# Terrarium.net
KiCad netlist of a schematic drawn in EAGLE
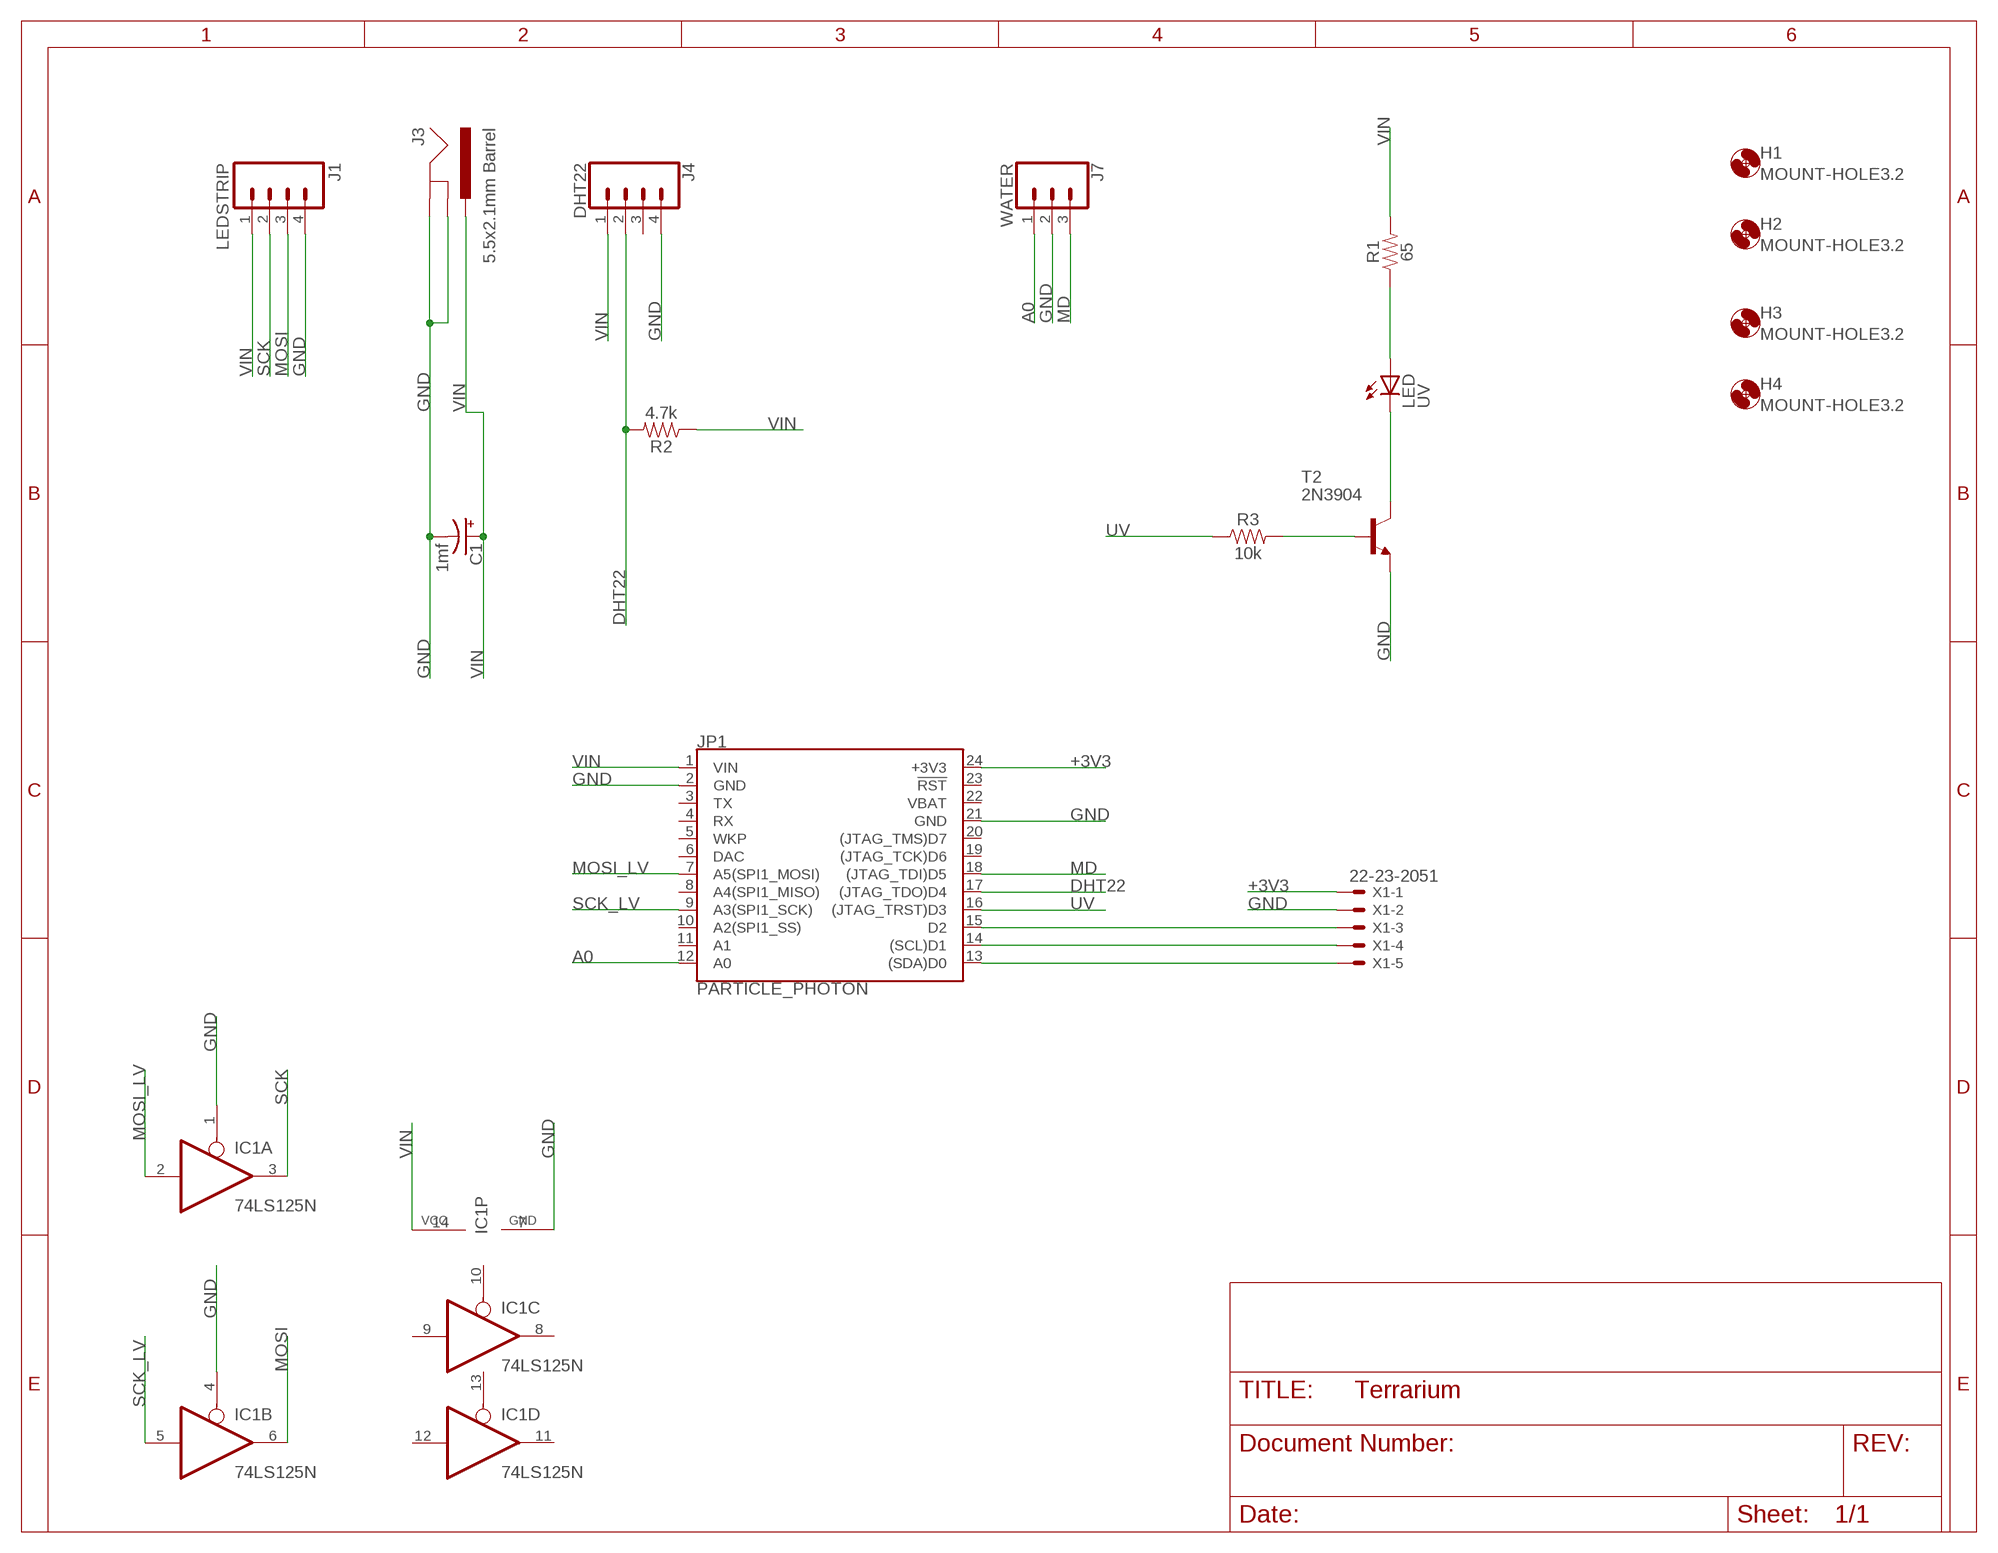
[diagram p0: schematic, sheet 1]

(export (version "E")
  (design (tool "Eeschema 10.0.6"))
  (components
    (comp (ref "C1")
      (value "1mf")
      (footprint "eagle-import:CPOL-RADIAL-5MM-10MM-KIT")
      (libsource (lib "eagle-import") (part "1000UF-RADIAL-5MM-35V-20%-KIT"))
    )
    (comp (ref "H1")
      (value "MOUNT-HOLE3.2")
      (footprint "eagle-import:3,2")
      (libsource (lib "eagle-import") (part "MOUNT-HOLE3.2"))
    )
    (comp (ref "H2")
      (value "MOUNT-HOLE3.2")
      (footprint "eagle-import:3,2")
      (libsource (lib "eagle-import") (part "MOUNT-HOLE3.2"))
    )
    (comp (ref "H3")
      (value "MOUNT-HOLE3.2")
      (footprint "eagle-import:3,2")
      (libsource (lib "eagle-import") (part "MOUNT-HOLE3.2"))
    )
    (comp (ref "H4")
      (value "MOUNT-HOLE3.2")
      (footprint "eagle-import:3,2")
      (libsource (lib "eagle-import") (part "MOUNT-HOLE3.2"))
    )
    (comp (ref "IC1")
      (value "74LS125N")
      (footprint "eagle-import:DIL14")
      (libsource (lib "eagle-import") (part "74125NLS"))
    )
    (comp (ref "J1")
      (value "LEDSTRIP")
      (footprint "eagle-import:1X04@1")
      (libsource (lib "eagle-import") (part "M04PTH"))
    )
    (comp (ref "J3")
      (value "5.5x2.1mm Barrel")
      (footprint "eagle-import:POWER_JACK_SMD")
      (libsource (lib "eagle-import") (part "POWER_JACKSMD"))
    )
    (comp (ref "J4")
      (value "DHT22")
      (footprint "eagle-import:1X04")
      (libsource (lib "eagle-import") (part "CONN_04"))
    )
    (comp (ref "J7")
      (value "WATER")
      (footprint "eagle-import:1X03")
      (libsource (lib "eagle-import") (part "CONN_03"))
    )
    (comp (ref "JP1")
      (value "PARTICLE_PHOTON")
      (footprint "eagle-import:PARTICLE_PHOTON")
      (libsource (lib "eagle-import") (part "PARTICLE_PHOTON"))
    )
    (comp (ref "LED")
      (value "UV")
      (footprint "eagle-import:LED5MM")
      (libsource (lib "eagle-import") (part "LED5MM"))
    )
    (comp (ref "R1")
      (value "65")
      (footprint "eagle-import:AXIAL-0.3")
      (libsource (lib "eagle-import") (part "100OHM-HORIZ-1/4W-1%"))
    )
    (comp (ref "R2")
      (value "4.7k")
      (footprint "eagle-import:AXIAL-0.3")
      (libsource (lib "eagle-import") (part "10KOHM-HORIZ-1/4W-5%"))
    )
    (comp (ref "R3")
      (value "10k")
      (footprint "eagle-import:AXIAL-0.3")
      (libsource (lib "eagle-import") (part "1KOHM-HORIZ-1/4W-5%"))
    )
    (comp (ref "T2")
      (value "2N3904")
      (footprint "eagle-import:TO92")
      (libsource (lib "eagle-import") (part "2N3904"))
    )
    (comp (ref "X1")
      (value "22-23-2051")
      (footprint "eagle-import:22-23-2051")
      (fields (field (name "MF") "MOLEX"))
      (libsource (lib "eagle-import") (part "22-23-2051"))
    )
  )
  (nets
    (net (code "1") (name "/+3V3") (class "Default")
      (node (ref "JP1") (pin "24") (pinfunction "+3V3_24") (pintype "power_in"))
      (node (ref "X1") (pin "1") (pinfunction "S_1") (pintype "passive"))
    )
    (net (code "2") (name "/A0") (class "Default")
      (node (ref "J7") (pin "1") (pinfunction "1_1") (pintype "passive"))
      (node (ref "JP1") (pin "12") (pinfunction "A0_12") (pintype "bidirectional"))
    )
    (net (code "3") (name "/DHT22") (class "Default")
      (node (ref "J4") (pin "2") (pinfunction "2_2") (pintype "passive"))
      (node (ref "JP1") (pin "17") (pinfunction "(JTAG_TDO)D4_17") (pintype "bidirectional"))
      (node (ref "R2") (pin "P$2") (pinfunction "2_P$2") (pintype "passive"))
    )
    (net (code "4") (name "/GND") (class "Default")
      (node (ref "C1") (pin "-") (pinfunction "-_-") (pintype "passive"))
      (node (ref "IC1") (pin "1") (pinfunction "OE_1") (pintype "input"))
      (node (ref "IC1") (pin "4") (pinfunction "OE_4") (pintype "input"))
      (node (ref "IC1") (pin "7") (pinfunction "GND_7") (pintype "power_in"))
      (node (ref "J1") (pin "4") (pinfunction "4_4") (pintype "passive"))
      (node (ref "J3") (pin "GND") (pinfunction "GNDBREAK_GND") (pintype "bidirectional"))
      (node (ref "J3") (pin "P$4") (pinfunction "GND_P$4") (pintype "bidirectional"))
      (node (ref "J4") (pin "4") (pinfunction "4_4") (pintype "passive"))
      (node (ref "J7") (pin "2") (pinfunction "2_2") (pintype "passive"))
      (node (ref "JP1") (pin "2") (pinfunction "GND_2") (pintype "power_in"))
      (node (ref "JP1") (pin "21") (pinfunction "GND_21") (pintype "power_in"))
      (node (ref "T2") (pin "3") (pinfunction "E_3") (pintype "passive"))
      (node (ref "X1") (pin "2") (pinfunction "S_2") (pintype "passive"))
    )
    (net (code "5") (name "/MD") (class "Default")
      (node (ref "J7") (pin "3") (pinfunction "3_3") (pintype "passive"))
      (node (ref "JP1") (pin "18") (pinfunction "(JTAG_TDI)D5_18") (pintype "bidirectional"))
    )
    (net (code "6") (name "/MOSI") (class "Default")
      (node (ref "IC1") (pin "6") (pinfunction "O_6") (pintype "tri_state"))
      (node (ref "J1") (pin "3") (pinfunction "3_3") (pintype "passive"))
    )
    (net (code "7") (name "/MOSI_LV") (class "Default")
      (node (ref "IC1") (pin "2") (pinfunction "I_2") (pintype "input"))
      (node (ref "JP1") (pin "7") (pinfunction "A5(SPI1_MOSI)_7") (pintype "bidirectional"))
    )
    (net (code "8") (name "/SCK") (class "Default")
      (node (ref "IC1") (pin "3") (pinfunction "O_3") (pintype "tri_state"))
      (node (ref "J1") (pin "2") (pinfunction "2_2") (pintype "passive"))
    )
    (net (code "9") (name "/SCK_LV") (class "Default")
      (node (ref "IC1") (pin "5") (pinfunction "I_5") (pintype "input"))
      (node (ref "JP1") (pin "9") (pinfunction "A3(SPI1_SCK)_9") (pintype "bidirectional"))
    )
    (net (code "10") (name "/UV") (class "Default")
      (node (ref "JP1") (pin "16") (pinfunction "(JTAG_TRST)D3_16") (pintype "bidirectional"))
      (node (ref "R3") (pin "P$1") (pinfunction "1_P$1") (pintype "passive"))
    )
    (net (code "11") (name "/VBAT") (class "Default")
      (node (ref "JP1") (pin "22") (pinfunction "VBAT_22") (pintype "power_in"))
    )
    (net (code "12") (name "/VIN") (class "Default")
      (node (ref "C1") (pin "+") (pinfunction "+_+") (pintype "passive"))
      (node (ref "IC1") (pin "14") (pinfunction "VCC_14") (pintype "power_in"))
      (node (ref "J1") (pin "1") (pinfunction "1_1") (pintype "passive"))
      (node (ref "J3") (pin "VIN0") (pinfunction "PWR_VIN0") (pintype "bidirectional"))
      (node (ref "J4") (pin "1") (pinfunction "1_1") (pintype "passive"))
      (node (ref "JP1") (pin "1") (pinfunction "VIN_1") (pintype "power_in"))
      (node (ref "R1") (pin "P$2") (pinfunction "2_P$2") (pintype "passive"))
      (node (ref "R2") (pin "P$1") (pinfunction "1_P$1") (pintype "passive"))
    )
    (net (code "13") (name "Net-(JP1-(SCL)D1)") (class "Default")
      (node (ref "JP1") (pin "14") (pinfunction "(SCL)D1_14") (pintype "bidirectional"))
      (node (ref "X1") (pin "4") (pinfunction "S_4") (pintype "passive"))
    )
    (net (code "14") (name "Net-(JP1-(SDA)D0)") (class "Default")
      (node (ref "JP1") (pin "13") (pinfunction "(SDA)D0_13") (pintype "bidirectional"))
      (node (ref "X1") (pin "5") (pinfunction "S_5") (pintype "passive"))
    )
    (net (code "15") (name "Net-(JP1-D2)") (class "Default")
      (node (ref "JP1") (pin "15") (pinfunction "D2_15") (pintype "bidirectional"))
      (node (ref "X1") (pin "3") (pinfunction "S_3") (pintype "passive"))
    )
    (net (code "16") (name "Net-(LED-C)") (class "Default")
      (node (ref "LED") (pin "K") (pinfunction "C_K") (pintype "passive"))
      (node (ref "T2") (pin "1") (pinfunction "C_1") (pintype "passive"))
    )
    (net (code "17") (name "Net-(R1-1)") (class "Default")
      (node (ref "LED") (pin "A") (pinfunction "A_A") (pintype "passive"))
      (node (ref "R1") (pin "P$1") (pinfunction "1_P$1") (pintype "passive"))
    )
    (net (code "18") (name "Net-(R3-2)") (class "Default")
      (node (ref "R3") (pin "P$2") (pinfunction "2_P$2") (pintype "passive"))
      (node (ref "T2") (pin "2") (pinfunction "B_2") (pintype "passive"))
    )
    (net (code "19") (name "unconnected-(IC1C-I-Pad9)") (class "Default")
      (node (ref "IC1") (pin "9") (pinfunction "I_9") (pintype "input"))
    )
    (net (code "20") (name "unconnected-(IC1C-O-Pad8)") (class "Default")
      (node (ref "IC1") (pin "8") (pinfunction "O_8") (pintype "tri_state"))
    )
    (net (code "21") (name "unconnected-(IC1C-OE-Pad10)") (class "Default")
      (node (ref "IC1") (pin "10") (pinfunction "OE_10") (pintype "input"))
    )
    (net (code "22") (name "unconnected-(IC1D-I-Pad12)") (class "Default")
      (node (ref "IC1") (pin "12") (pinfunction "I_12") (pintype "input"))
    )
    (net (code "23") (name "unconnected-(IC1D-O-Pad11)") (class "Default")
      (node (ref "IC1") (pin "11") (pinfunction "O_11") (pintype "tri_state"))
    )
    (net (code "24") (name "unconnected-(IC1D-OE-Pad13)") (class "Default")
      (node (ref "IC1") (pin "13") (pinfunction "OE_13") (pintype "input"))
    )
    (net (code "25") (name "unconnected-(J4-Pad3)") (class "Default")
      (node (ref "J4") (pin "3") (pinfunction "3_3") (pintype "passive"))
    )
    (net (code "26") (name "unconnected-(JP1-(JTAG_TCK)D6-Pad19)") (class "Default")
      (node (ref "JP1") (pin "19") (pinfunction "(JTAG_TCK)D6_19") (pintype "bidirectional"))
    )
    (net (code "27") (name "unconnected-(JP1-(JTAG_TMS)D7-Pad20)") (class "Default")
      (node (ref "JP1") (pin "20") (pinfunction "(JTAG_TMS)D7_20") (pintype "bidirectional"))
    )
    (net (code "28") (name "unconnected-(JP1-A1-Pad11)") (class "Default")
      (node (ref "JP1") (pin "11") (pinfunction "A1_11") (pintype "bidirectional"))
    )
    (net (code "29") (name "unconnected-(JP1-A2(SPI1_SS)-Pad10)") (class "Default")
      (node (ref "JP1") (pin "10") (pinfunction "A2(SPI1_SS)_10") (pintype "bidirectional"))
    )
    (net (code "30") (name "unconnected-(JP1-A4(SPI1_MISO)-Pad8)") (class "Default")
      (node (ref "JP1") (pin "8") (pinfunction "A4(SPI1_MISO)_8") (pintype "bidirectional"))
    )
    (net (code "31") (name "unconnected-(JP1-DAC-Pad6)") (class "Default")
      (node (ref "JP1") (pin "6") (pinfunction "DAC_6") (pintype "bidirectional"))
    )
    (net (code "32") (name "unconnected-(JP1-RX-Pad4)") (class "Default")
      (node (ref "JP1") (pin "4") (pinfunction "RX_4") (pintype "bidirectional"))
    )
    (net (code "33") (name "unconnected-(JP1-TX-Pad3)") (class "Default")
      (node (ref "JP1") (pin "3") (pinfunction "TX_3") (pintype "bidirectional"))
    )
    (net (code "34") (name "unconnected-(JP1-WKP-Pad5)") (class "Default")
      (node (ref "JP1") (pin "5") (pinfunction "WKP_5") (pintype "bidirectional"))
    )
    (net (code "35") (name "unconnected-(JP1-~{RST}-Pad23)") (class "Default")
      (node (ref "JP1") (pin "23") (pinfunction "~{RST}_23") (pintype "bidirectional"))
    )
  )
)
